# power.net
KiCad netlist of a schematic drawn in EAGLE
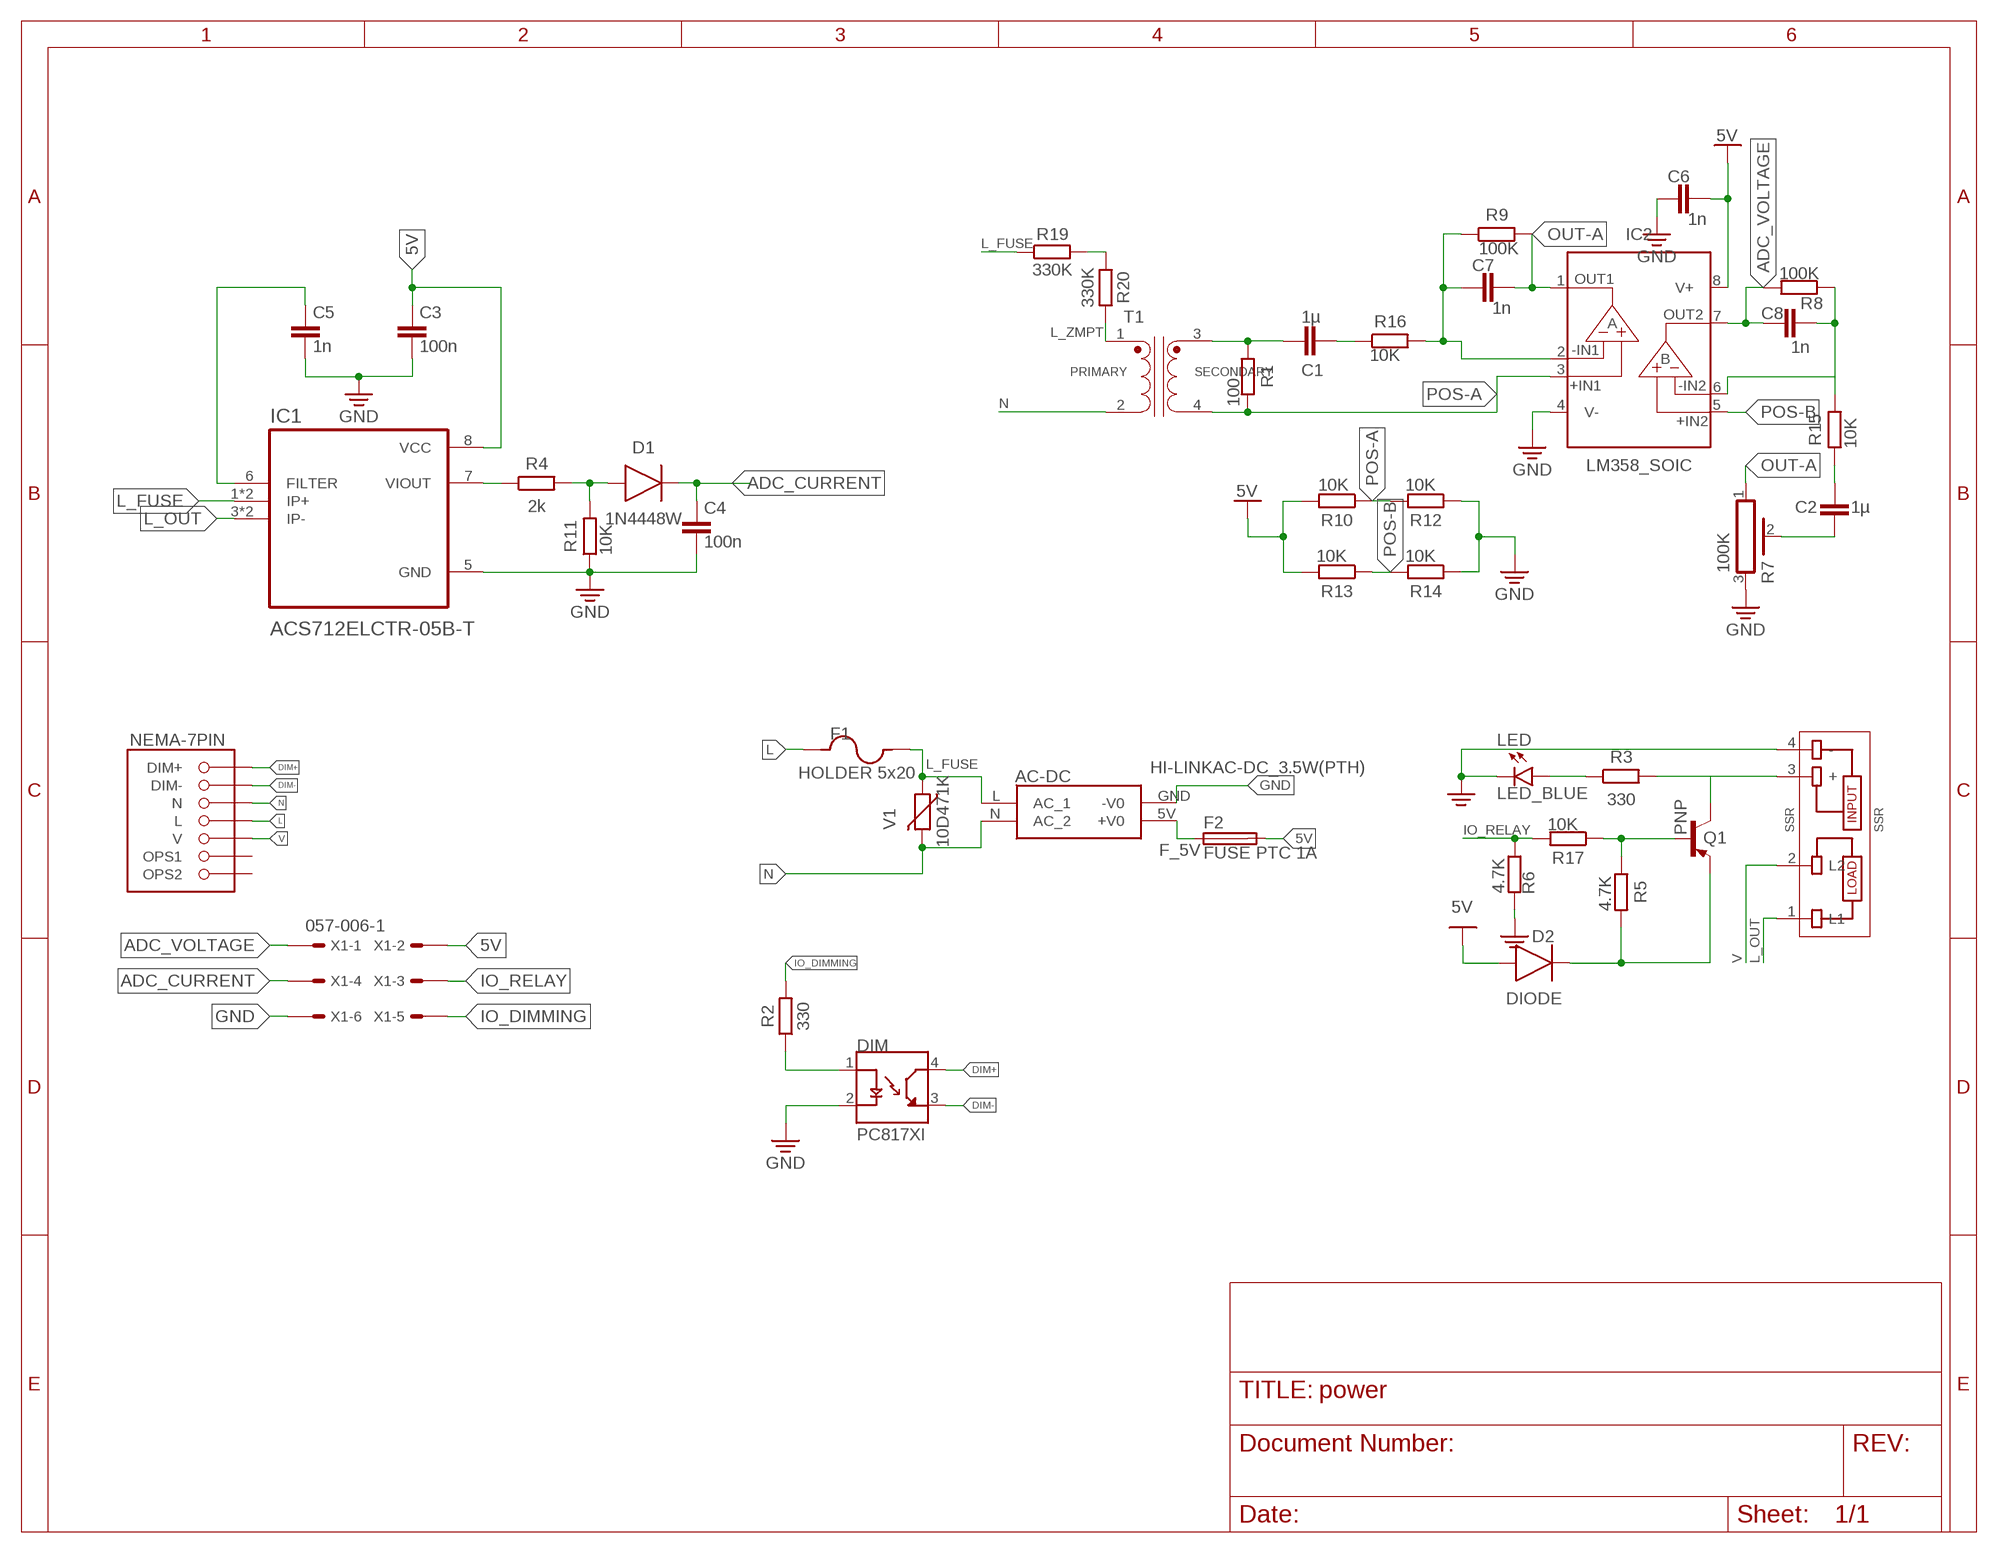
[diagram p0: schematic, sheet 1]

(export (version "E")
  (design (tool "Eeschema 10.0.6"))
  (components
    (comp (ref "AC-DC")
      (value "HI-LINKAC-DC_3.5W(PTH)")
      (footprint "eagle-import:AC-DC_3.5W(PTH)")
      (libsource (lib "eagle-import") (part "HI-LINKAC-DC_3.5W(PTH)"))
    )
    (comp (ref "C1")
      (value "1µ")
      (footprint "eagle-import:CAPC2012X110")
      (libsource (lib "eagle-import") (part "CCHIP-0805(2012-METRIC)_"))
    )
    (comp (ref "C2")
      (value "1µ")
      (footprint "eagle-import:CAPC2012X110")
      (libsource (lib "eagle-import") (part "CCHIP-0805(2012-METRIC)_"))
    )
    (comp (ref "C3")
      (value "100n")
      (footprint "eagle-import:CAPC2012X110")
      (libsource (lib "eagle-import") (part "CCHIP-0805(2012-METRIC)_"))
    )
    (comp (ref "C4")
      (value "100n")
      (footprint "eagle-import:CAPC2012X110")
      (libsource (lib "eagle-import") (part "CCHIP-0805(2012-METRIC)_"))
    )
    (comp (ref "C5")
      (value "1n")
      (footprint "eagle-import:CAPC2012X110")
      (libsource (lib "eagle-import") (part "CCHIP-0805(2012-METRIC)_"))
    )
    (comp (ref "C6")
      (value "1n")
      (footprint "eagle-import:CAPC2012X110")
      (libsource (lib "eagle-import") (part "CCHIP-0805(2012-METRIC)_"))
    )
    (comp (ref "C7")
      (value "1n")
      (footprint "eagle-import:CAPC2012X110")
      (libsource (lib "eagle-import") (part "CCHIP-0805(2012-METRIC)_"))
    )
    (comp (ref "C8")
      (value "1n")
      (footprint "eagle-import:CAPC2012X110")
      (libsource (lib "eagle-import") (part "CCHIP-0805(2012-METRIC)_"))
    )
    (comp (ref "D1")
      (value "1N4448W")
      (footprint "eagle-import:SOD3715X135")
      (fields (field (name "MANUFACTURER") "Diodes Incorporated"))
      (libsource (lib "eagle-import") (part "DIODE__SOD123G1N4148W-7-F"))
    )
    (comp (ref "D2")
      (value "DIODE")
      (footprint "eagle-import:DIOM5226X290N")
      (libsource (lib "eagle-import") (part "DIODEDO-214AC(SMA)"))
    )
    (comp (ref "DIM")
      (value "PC817XI")
      (footprint "eagle-import:SOIC254P975X460-4N")
      (fields (field (name "MF") "Sharp"))
      (libsource (lib "eagle-import") (part "PC817XI"))
    )
    (comp (ref "F1")
      (value "HOLDER 5x20")
      (footprint "eagle-import:4527")
      (fields
        (field (name "MANUFACTURER") "Keystone Electronics")
        (field (name "MPN") "4527")
        (field (name "CREATED_BY") "PCBLayout.com")
      )
      (libsource (lib "eagle-import") (part "4527"))
    )
    (comp (ref "F2")
      (value "FUSE PTC 1A")
      (footprint "eagle-import:FUSC3215X82N")
      (libsource (lib "eagle-import") (part "FUSECHIP-1206(3216-METRIC)_"))
    )
    (comp (ref "IC1")
      (value "ACS712ELCTR-05B-T")
      (footprint "eagle-import:SOIC127P600X175-8N@1")
      (libsource (lib "eagle-import") (part "ACS712ELCTR-05B-T"))
    )
    (comp (ref "IC2")
      (value "LM358_SOIC")
      (footprint "eagle-import:SOIC127P600X175-8N")
      (fields (field (name "MANUFACTURER") "Generic"))
      (libsource (lib "eagle-import") (part "LM358_SOIC"))
    )
    (comp (ref "LED")
      (value "LED_BLUE")
      (footprint "eagle-import:LEDC2012X110N_FLAT-B")
      (libsource (lib "eagle-import") (part "CHIP-FLAT-B_0805"))
    )
    (comp (ref "NEMA-7PIN")
      (value "NEMA-7P")
      (footprint "eagle-import:NEMA-7P")
      (libsource (lib "eagle-import") (part "NEMA-7P"))
    )
    (comp (ref "Q1")
      (value "PNP")
      (footprint "eagle-import:SOT95P237X112-3N")
      (libsource (lib "eagle-import") (part "PNPSOT23-BEC_"))
    )
    (comp (ref "R1")
      (value "100")
      (footprint "eagle-import:RESC2012X65")
      (libsource (lib "eagle-import") (part "RCHIP-0805(2012-METRIC)_"))
    )
    (comp (ref "R2")
      (value "330")
      (footprint "eagle-import:RESC2012X65")
      (libsource (lib "eagle-import") (part "RCHIP-0805(2012-METRIC)_"))
    )
    (comp (ref "R3")
      (value "330")
      (footprint "eagle-import:RESC2012X65")
      (libsource (lib "eagle-import") (part "RCHIP-0805(2012-METRIC)_"))
    )
    (comp (ref "R4")
      (value "2k")
      (footprint "eagle-import:RESC2012X65")
      (libsource (lib "eagle-import") (part "RCHIP-0805(2012-METRIC)_"))
    )
    (comp (ref "R5")
      (value "4.7K")
      (footprint "eagle-import:RESC2012X65")
      (libsource (lib "eagle-import") (part "RCHIP-0805(2012-METRIC)_"))
    )
    (comp (ref "R6")
      (value "4.7K")
      (footprint "eagle-import:RESC2012X65")
      (libsource (lib "eagle-import") (part "RCHIP-0805(2012-METRIC)_"))
    )
    (comp (ref "R7")
      (value "100K")
      (footprint "eagle-import:PV36W")
      (fields (field (name "MANUFACTURER") "BOURNS") (field (name "MPN") "PV36W"))
      (libsource (lib "eagle-import") (part "PV36W"))
    )
    (comp (ref "R8")
      (value "100K")
      (footprint "eagle-import:RESC2012X65")
      (libsource (lib "eagle-import") (part "RCHIP-0805(2012-METRIC)_"))
    )
    (comp (ref "R9")
      (value "100K")
      (footprint "eagle-import:RESC2012X65")
      (libsource (lib "eagle-import") (part "RCHIP-0805(2012-METRIC)_"))
    )
    (comp (ref "R10")
      (value "10K")
      (footprint "eagle-import:RESC2012X65")
      (libsource (lib "eagle-import") (part "RCHIP-0805(2012-METRIC)_"))
    )
    (comp (ref "R11")
      (value "10K")
      (footprint "eagle-import:RESC2012X65")
      (libsource (lib "eagle-import") (part "RCHIP-0805(2012-METRIC)_"))
    )
    (comp (ref "R12")
      (value "10K")
      (footprint "eagle-import:RESC2012X65")
      (libsource (lib "eagle-import") (part "RCHIP-0805(2012-METRIC)_"))
    )
    (comp (ref "R13")
      (value "10K")
      (footprint "eagle-import:RESC2012X65")
      (libsource (lib "eagle-import") (part "RCHIP-0805(2012-METRIC)_"))
    )
    (comp (ref "R14")
      (value "10K")
      (footprint "eagle-import:RESC2012X65")
      (libsource (lib "eagle-import") (part "RCHIP-0805(2012-METRIC)_"))
    )
    (comp (ref "R15")
      (value "10K")
      (footprint "eagle-import:RESC2012X65")
      (libsource (lib "eagle-import") (part "RCHIP-0805(2012-METRIC)_"))
    )
    (comp (ref "R16")
      (value "10K")
      (footprint "eagle-import:RESC2012X65")
      (libsource (lib "eagle-import") (part "RCHIP-0805(2012-METRIC)_"))
    )
    (comp (ref "R17")
      (value "10K")
      (footprint "eagle-import:RESC2012X65")
      (libsource (lib "eagle-import") (part "RCHIP-0805(2012-METRIC)_"))
    )
    (comp (ref "R19")
      (value "330K")
      (footprint "eagle-import:RESAD724W46L381D178B")
      (libsource (lib "eagle-import") (part "RAXIAL-7.2MM-PITCH_"))
    )
    (comp (ref "R20")
      (value "330K")
      (footprint "eagle-import:RESAD724W46L381D178B")
      (libsource (lib "eagle-import") (part "RAXIAL-7.2MM-PITCH_"))
    )
    (comp (ref "SSR")
      (value "SSR")
      (footprint "eagle-import:SSR_G3MB-202P")
      (fields (field (name "MANUFACTURER") "Omron"))
      (libsource (lib "eagle-import") (part "SSR"))
    )
    (comp (ref "T1")
      (value "ZMPT101B")
      (footprint "eagle-import:ZMPT101B")
      (fields (field (name "MANUFACTURER") "Qingxian Zeming Langxi Electronic"))
      (libsource (lib "eagle-import") (part "ZMPT101B"))
    )
    (comp (ref "V1")
      (value "10D471K")
      (footprint "eagle-import:MOV-10D561")
      (libsource (lib "eagle-import") (part "VARISTOR"))
    )
    (comp (ref "X1")
      (value "057-006-1")
      (footprint "eagle-import:057-006-1")
      (libsource (lib "eagle-import") (part "057-006-1"))
    )
  )
  (nets
    (net (code "1") (name "/F_5V") (class "Default")
      (node (ref "AC-DC") (pin "5V") (pinfunction "+V0_5V") (pintype "bidirectional"))
      (node (ref "F2") (pin "1") (pinfunction "1_1") (pintype "passive"))
    )
    (net (code "2") (name "/L_ZMPT") (class "Default")
      (node (ref "R20") (pin "2") (pinfunction "2_2") (pintype "passive"))
      (node (ref "T1") (pin "1") (pinfunction "1_1") (pintype "passive"))
    )
    (net (code "3") (name "5V") (class "Default")
      (node (ref "C3") (pin "1") (pinfunction "1_1") (pintype "passive"))
      (node (ref "C6") (pin "2") (pinfunction "2_2") (pintype "passive"))
      (node (ref "D2") (pin "2") (pinfunction "A_2") (pintype "passive"))
      (node (ref "F2") (pin "2") (pinfunction "2_2") (pintype "passive"))
      (node (ref "IC1") (pin "8") (pinfunction "VCC_8") (pintype "power_in"))
      (node (ref "IC2") (pin "8") (pinfunction "V+_8") (pintype "bidirectional"))
      (node (ref "R10") (pin "2") (pinfunction "2_2") (pintype "passive"))
      (node (ref "R13") (pin "2") (pinfunction "2_2") (pintype "passive"))
      (node (ref "X1") (pin "2") (pinfunction "S_2") (pintype "passive"))
    )
    (net (code "4") (name "ADC_CURRENT") (class "Default")
      (node (ref "C4") (pin "1") (pinfunction "1_1") (pintype "passive"))
      (node (ref "D1") (pin "1") (pinfunction "C_1") (pintype "passive"))
      (node (ref "X1") (pin "4") (pinfunction "S_4") (pintype "passive"))
    )
    (net (code "5") (name "ADC_VOLTAGE") (class "Default")
      (node (ref "C8") (pin "1") (pinfunction "1_1") (pintype "passive"))
      (node (ref "IC2") (pin "7") (pinfunction "OUT2_7") (pintype "passive"))
      (node (ref "R8") (pin "2") (pinfunction "2_2") (pintype "passive"))
      (node (ref "X1") (pin "1") (pinfunction "S_1") (pintype "passive"))
    )
    (net (code "6") (name "DIM+") (class "Default")
      (node (ref "DIM") (pin "4") (pinfunction "CT_4") (pintype "passive"))
      (node (ref "NEMA-7PIN") (pin "DIM+") (pinfunction "DIM+_DIM+") (pintype "output"))
    )
    (net (code "7") (name "DIM-") (class "Default")
      (node (ref "DIM") (pin "3") (pinfunction "ET_3") (pintype "passive"))
      (node (ref "NEMA-7PIN") (pin "DIM-") (pinfunction "DIM-_DIM-") (pintype "output"))
    )
    (net (code "8") (name "GND") (class "Default")
      (node (ref "AC-DC") (pin "GND") (pinfunction "-V0_GND") (pintype "bidirectional"))
      (node (ref "C3") (pin "2") (pinfunction "2_2") (pintype "passive"))
      (node (ref "C4") (pin "2") (pinfunction "2_2") (pintype "passive"))
      (node (ref "C5") (pin "2") (pinfunction "2_2") (pintype "passive"))
      (node (ref "C6") (pin "1") (pinfunction "1_1") (pintype "passive"))
      (node (ref "DIM") (pin "2") (pinfunction "C_2") (pintype "passive"))
      (node (ref "IC1") (pin "5") (pinfunction "GND_5") (pintype "power_in"))
      (node (ref "IC2") (pin "4") (pinfunction "V-_4") (pintype "bidirectional"))
      (node (ref "LED") (pin "C") (pinfunction "C_C") (pintype "passive"))
      (node (ref "R11") (pin "1") (pinfunction "1_1") (pintype "passive"))
      (node (ref "R12") (pin "1") (pinfunction "1_1") (pintype "passive"))
      (node (ref "R14") (pin "1") (pinfunction "1_1") (pintype "passive"))
      (node (ref "R6") (pin "2") (pinfunction "2_2") (pintype "passive"))
      (node (ref "R7") (pin "3") (pinfunction "P$3_3") (pintype "passive"))
      (node (ref "SSR") (pin "4") (pinfunction "-_4") (pintype "power_in"))
      (node (ref "X1") (pin "6") (pinfunction "S_6") (pintype "passive"))
    )
    (net (code "9") (name "IO_DIMMING") (class "Default")
      (node (ref "R2") (pin "2") (pinfunction "2_2") (pintype "passive"))
      (node (ref "X1") (pin "5") (pinfunction "S_5") (pintype "passive"))
    )
    (net (code "10") (name "IO_RELAY") (class "Default")
      (node (ref "R17") (pin "2") (pinfunction "2_2") (pintype "passive"))
      (node (ref "R6") (pin "1") (pinfunction "1_1") (pintype "passive"))
      (node (ref "X1") (pin "3") (pinfunction "S_3") (pintype "passive"))
    )
    (net (code "11") (name "L") (class "Default")
      (node (ref "F1") (pin "1") (pinfunction "1_1") (pintype "passive"))
      (node (ref "NEMA-7PIN") (pin "L") (pinfunction "L_L") (pintype "output"))
    )
    (net (code "12") (name "L_FUSE") (class "Default")
      (node (ref "AC-DC") (pin "L") (pinfunction "AC_1_L") (pintype "bidirectional"))
      (node (ref "F1") (pin "2") (pinfunction "2_2") (pintype "passive"))
      (node (ref "IC1") (pin "1") (pinfunction "IP+_1") (pintype "input"))
      (node (ref "IC1") (pin "2") (pinfunction "IP+_2") (pintype "input"))
      (node (ref "R19") (pin "1") (pinfunction "1_1") (pintype "passive"))
      (node (ref "V1") (pin "1") (pinfunction "1_1") (pintype "passive"))
    )
    (net (code "13") (name "L_OUT") (class "Default")
      (node (ref "IC1") (pin "3") (pinfunction "IP-_3") (pintype "input"))
      (node (ref "IC1") (pin "4") (pinfunction "IP-_4") (pintype "input"))
      (node (ref "SSR") (pin "1") (pinfunction "L1_1") (pintype "power_in"))
    )
    (net (code "14") (name "N") (class "Default")
      (node (ref "AC-DC") (pin "N") (pinfunction "AC_2_N") (pintype "bidirectional"))
      (node (ref "NEMA-7PIN") (pin "N") (pinfunction "N_N") (pintype "output"))
      (node (ref "T1") (pin "2") (pinfunction "2_2") (pintype "passive"))
      (node (ref "V1") (pin "2") (pinfunction "2_2") (pintype "passive"))
    )
    (net (code "15") (name "Net-(C1-Pad1)") (class "Default")
      (node (ref "C1") (pin "1") (pinfunction "1_1") (pintype "passive"))
      (node (ref "R1") (pin "1") (pinfunction "1_1") (pintype "passive"))
      (node (ref "T1") (pin "3") (pinfunction "3_3") (pintype "passive"))
    )
    (net (code "16") (name "Net-(C1-Pad2)") (class "Default")
      (node (ref "C1") (pin "2") (pinfunction "2_2") (pintype "passive"))
      (node (ref "R16") (pin "1") (pinfunction "1_1") (pintype "passive"))
    )
    (net (code "17") (name "Net-(C2-Pad2)") (class "Default")
      (node (ref "C2") (pin "2") (pinfunction "2_2") (pintype "passive"))
      (node (ref "R15") (pin "1") (pinfunction "1_1") (pintype "passive"))
    )
    (net (code "18") (name "Net-(D1-A)") (class "Default")
      (node (ref "D1") (pin "2") (pinfunction "A_2") (pintype "passive"))
      (node (ref "R11") (pin "2") (pinfunction "2_2") (pintype "passive"))
      (node (ref "R4") (pin "2") (pinfunction "2_2") (pintype "passive"))
    )
    (net (code "19") (name "Net-(D2-C)") (class "Default")
      (node (ref "D2") (pin "1") (pinfunction "C_1") (pintype "passive"))
      (node (ref "Q1") (pin "2") (pinfunction "E_2") (pintype "passive"))
      (node (ref "R5") (pin "2") (pinfunction "2_2") (pintype "passive"))
    )
    (net (code "20") (name "Net-(DIM-A)") (class "Default")
      (node (ref "DIM") (pin "1") (pinfunction "A_1") (pintype "passive"))
      (node (ref "R2") (pin "1") (pinfunction "1_1") (pintype "passive"))
    )
    (net (code "21") (name "Net-(IC1-FILTER)") (class "Default")
      (node (ref "C5") (pin "1") (pinfunction "1_1") (pintype "passive"))
      (node (ref "IC1") (pin "6") (pinfunction "FILTER_6") (pintype "input"))
    )
    (net (code "22") (name "Net-(IC1-VIOUT)") (class "Default")
      (node (ref "IC1") (pin "7") (pinfunction "VIOUT_7") (pintype "output"))
      (node (ref "R4") (pin "1") (pinfunction "1_1") (pintype "passive"))
    )
    (net (code "23") (name "Net-(IC2--IN1)") (class "Default")
      (node (ref "C7") (pin "1") (pinfunction "1_1") (pintype "passive"))
      (node (ref "IC2") (pin "2") (pinfunction "-IN1_2") (pintype "input"))
      (node (ref "R16") (pin "2") (pinfunction "2_2") (pintype "passive"))
      (node (ref "R9") (pin "1") (pinfunction "1_1") (pintype "passive"))
    )
    (net (code "24") (name "Net-(IC2--IN2)") (class "Default")
      (node (ref "C8") (pin "2") (pinfunction "2_2") (pintype "passive"))
      (node (ref "IC2") (pin "6") (pinfunction "-IN2_6") (pintype "passive"))
      (node (ref "R15") (pin "2") (pinfunction "2_2") (pintype "passive"))
      (node (ref "R8") (pin "1") (pinfunction "1_1") (pintype "passive"))
    )
    (net (code "25") (name "Net-(LED-PadA)") (class "Default")
      (node (ref "LED") (pin "A") (pinfunction "A_A") (pintype "passive"))
      (node (ref "R3") (pin "1") (pinfunction "1_1") (pintype "passive"))
    )
    (net (code "26") (name "Net-(Q1-B)") (class "Default")
      (node (ref "Q1") (pin "1") (pinfunction "B_1") (pintype "passive"))
      (node (ref "R17") (pin "1") (pinfunction "1_1") (pintype "passive"))
      (node (ref "R5") (pin "1") (pinfunction "1_1") (pintype "passive"))
    )
    (net (code "27") (name "Net-(Q1-C)") (class "Default")
      (node (ref "Q1") (pin "3") (pinfunction "C_3") (pintype "passive"))
      (node (ref "R3") (pin "2") (pinfunction "2_2") (pintype "passive"))
      (node (ref "SSR") (pin "3") (pinfunction "+_3") (pintype "power_in"))
    )
    (net (code "28") (name "Net-(R7-P$2)") (class "Default")
      (node (ref "C2") (pin "1") (pinfunction "1_1") (pintype "passive"))
      (node (ref "R7") (pin "2") (pinfunction "P$2_2") (pintype "passive"))
    )
    (net (code "29") (name "Net-(R19-Pad2)") (class "Default")
      (node (ref "R19") (pin "2") (pinfunction "2_2") (pintype "passive"))
      (node (ref "R20") (pin "1") (pinfunction "1_1") (pintype "passive"))
    )
    (net (code "30") (name "OUT-A") (class "Default")
      (node (ref "C7") (pin "2") (pinfunction "2_2") (pintype "passive"))
      (node (ref "IC2") (pin "1") (pinfunction "OUT1_1") (pintype "passive"))
      (node (ref "R7") (pin "1") (pinfunction "P$1_1") (pintype "passive"))
      (node (ref "R9") (pin "2") (pinfunction "2_2") (pintype "passive"))
    )
    (net (code "31") (name "POS-A") (class "Default")
      (node (ref "IC2") (pin "3") (pinfunction "+IN1_3") (pintype "input"))
      (node (ref "R1") (pin "2") (pinfunction "2_2") (pintype "passive"))
      (node (ref "R10") (pin "1") (pinfunction "1_1") (pintype "passive"))
      (node (ref "R12") (pin "2") (pinfunction "2_2") (pintype "passive"))
      (node (ref "T1") (pin "4") (pinfunction "4_4") (pintype "passive"))
    )
    (net (code "32") (name "POS-B") (class "Default")
      (node (ref "IC2") (pin "5") (pinfunction "+IN2_5") (pintype "passive"))
      (node (ref "R13") (pin "1") (pinfunction "1_1") (pintype "passive"))
      (node (ref "R14") (pin "2") (pinfunction "2_2") (pintype "passive"))
    )
    (net (code "33") (name "V") (class "Default")
      (node (ref "NEMA-7PIN") (pin "V") (pinfunction "V_V") (pintype "output"))
      (node (ref "SSR") (pin "2") (pinfunction "L2_2") (pintype "power_in"))
    )
    (net (code "34") (name "unconnected-(NEMA-7PIN-PadOPS1)") (class "Default")
      (node (ref "NEMA-7PIN") (pin "OPS1") (pinfunction "OPS1_OPS1") (pintype "output"))
    )
    (net (code "35") (name "unconnected-(NEMA-7PIN-PadOPS2)") (class "Default")
      (node (ref "NEMA-7PIN") (pin "OPS2") (pinfunction "OPS2_OPS2") (pintype "output"))
    )
  )
)
